# ardOnTimer.net
KiCad netlist of a schematic drawn in EAGLE
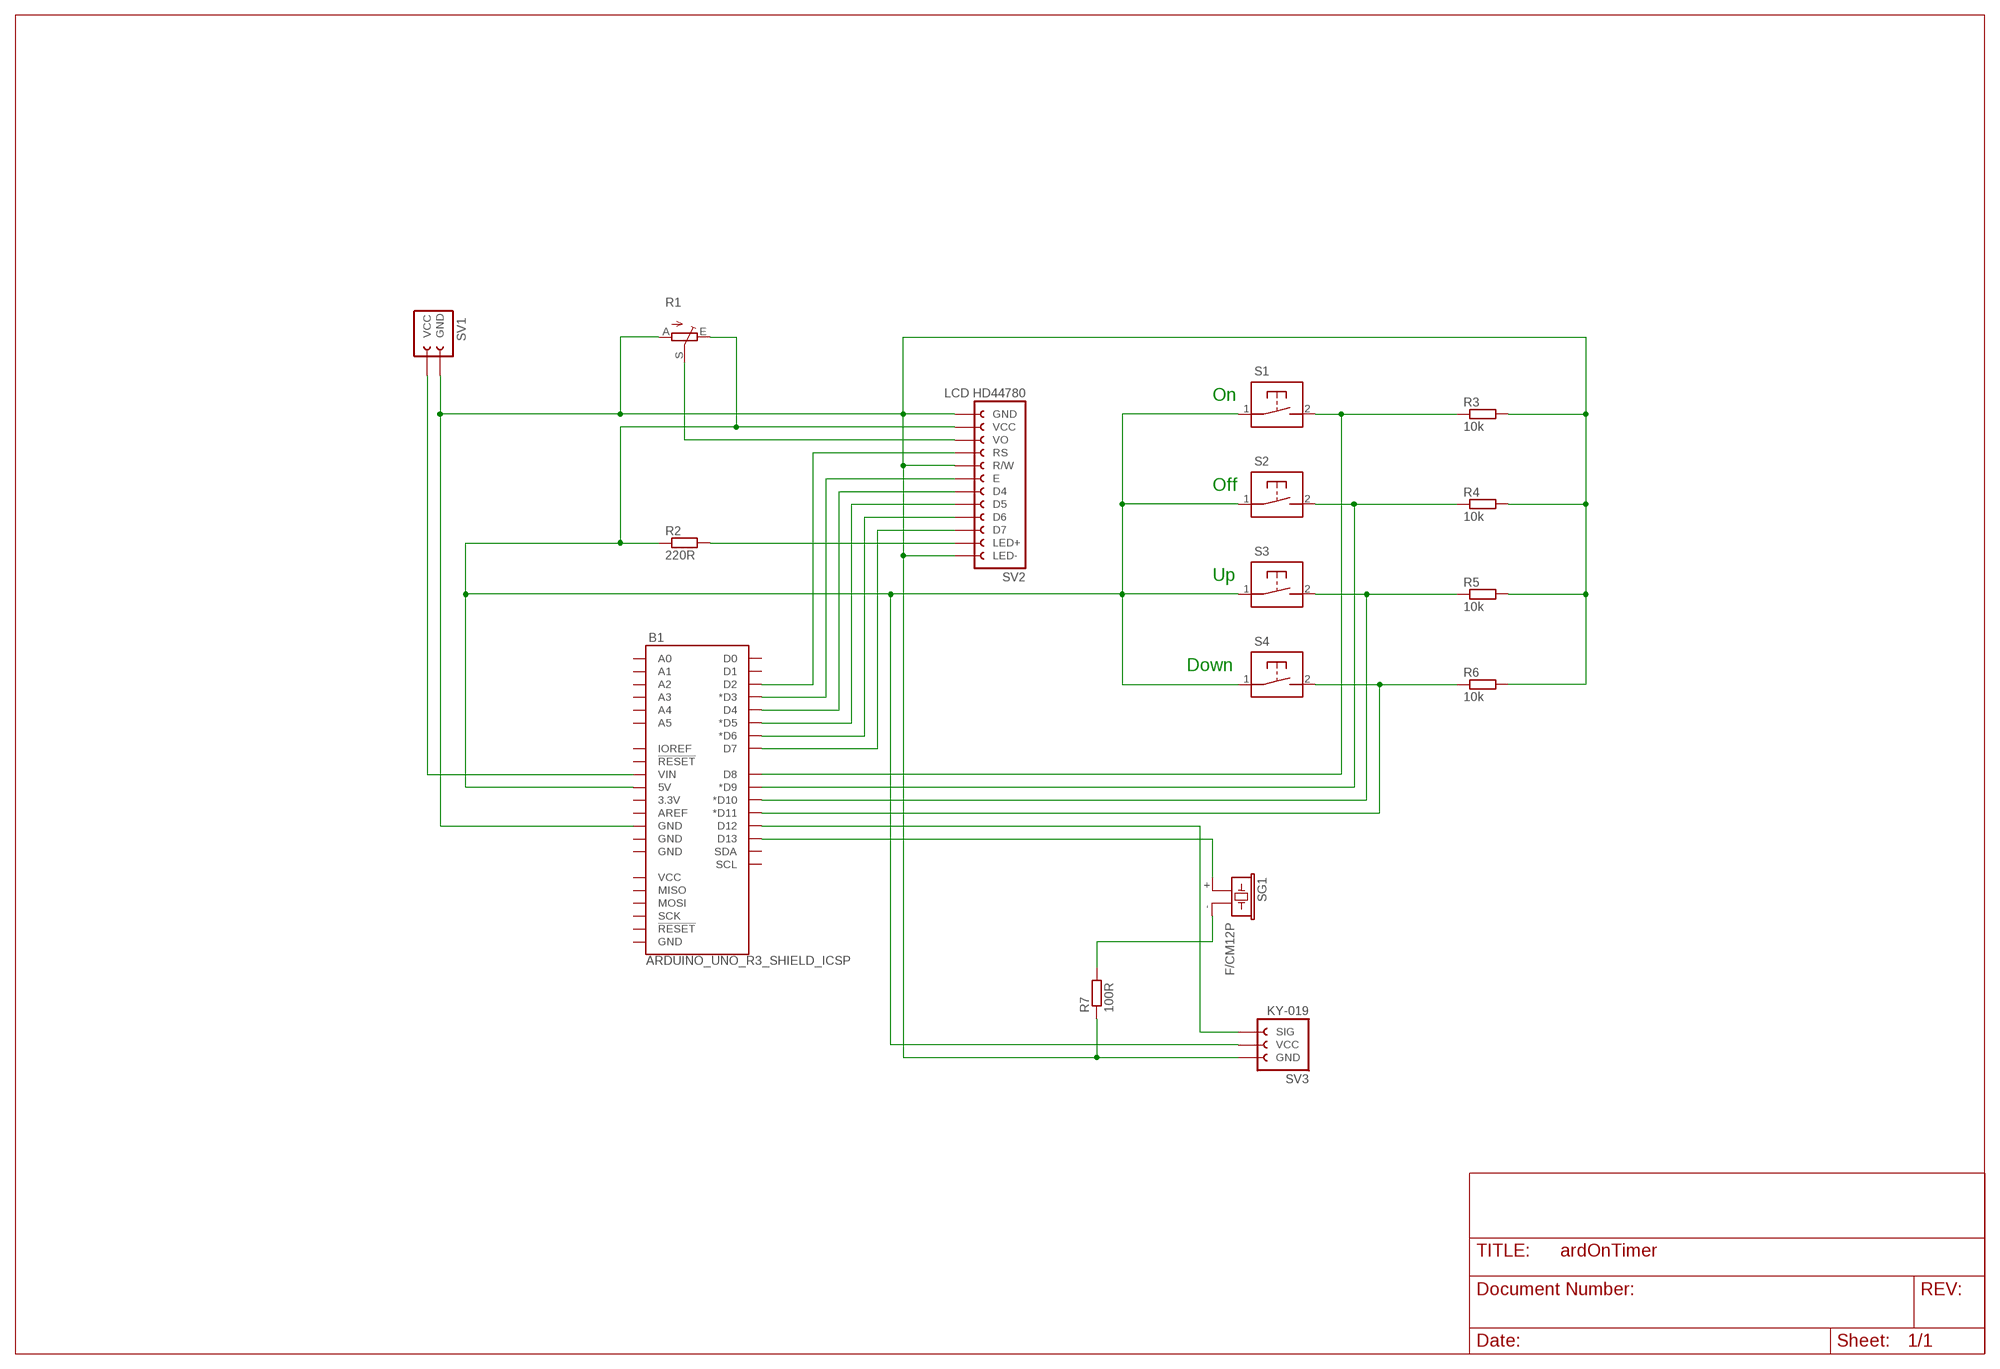
[diagram p0: schematic, sheet 1]

(export (version "E")
  (design (tool "Eeschema 10.0.6"))
  (components
    (comp (ref "B1")
      (value "ARDUINO_UNO_R3_SHIELD_ICSP")
      (footprint "eagle-import:UNO_R3_SHIELD_ICSP")
      (libsource (lib "eagle-import") (part "ARDUINO_UNO_R3_SHIELD_ICSP"))
    )
    (comp (ref "R1")
      (value "POTENTIOMETER_CA6VCA6V")
      (footprint "eagle-import:CA6V")
      (libsource (lib "eagle-import") (part "POTENTIOMETER_CA6VCA6V"))
    )
    (comp (ref "R2")
      (value "220R")
      (footprint "eagle-import:0204_7")
      (libsource (lib "eagle-import") (part "R-EU_0204/7"))
    )
    (comp (ref "R3")
      (value "10k")
      (footprint "eagle-import:0204_7")
      (libsource (lib "eagle-import") (part "R-EU_0204/7"))
    )
    (comp (ref "R4")
      (value "10k")
      (footprint "eagle-import:0204_7")
      (libsource (lib "eagle-import") (part "R-EU_0204/7"))
    )
    (comp (ref "R5")
      (value "10k")
      (footprint "eagle-import:0204_7")
      (libsource (lib "eagle-import") (part "R-EU_0204/7"))
    )
    (comp (ref "R6")
      (value "10k")
      (footprint "eagle-import:0204_7")
      (libsource (lib "eagle-import") (part "R-EU_0204/7"))
    )
    (comp (ref "R7")
      (value "100R")
      (footprint "eagle-import:0204_7")
      (libsource (lib "eagle-import") (part "R-EU_0204/7"))
    )
    (comp (ref "S1")
      (value "NO_SWITCH_2-PIN-FEMALE_HEADER")
      (footprint "eagle-import:NO_SWITCH_2-PIN-FEMALE_HEADER")
      (fields (field (name "MPN") "B3F-3100"))
      (libsource (lib "eagle-import") (part "NO_SWITCH_2-PIN-FEMALE_HEADER"))
    )
    (comp (ref "S2")
      (value "NO_SWITCH_2-PIN-FEMALE_HEADER")
      (footprint "eagle-import:NO_SWITCH_2-PIN-FEMALE_HEADER")
      (fields (field (name "MPN") "B3F-3100"))
      (libsource (lib "eagle-import") (part "NO_SWITCH_2-PIN-FEMALE_HEADER"))
    )
    (comp (ref "S3")
      (value "NO_SWITCH_2-PIN-FEMALE_HEADER")
      (footprint "eagle-import:NO_SWITCH_2-PIN-FEMALE_HEADER")
      (fields (field (name "MPN") "B3F-3100"))
      (libsource (lib "eagle-import") (part "NO_SWITCH_2-PIN-FEMALE_HEADER"))
    )
    (comp (ref "S4")
      (value "NO_SWITCH_2-PIN-FEMALE_HEADER")
      (footprint "eagle-import:NO_SWITCH_2-PIN-FEMALE_HEADER")
      (fields (field (name "MPN") "B3F-3100"))
      (libsource (lib "eagle-import") (part "NO_SWITCH_2-PIN-FEMALE_HEADER"))
    )
    (comp (ref "SG1")
      (value "F/CM12P")
      (footprint "eagle-import:F_CM12P")
      (libsource (lib "eagle-import") (part "F/CM12P"))
    )
    (comp (ref "SV1")
      (value "POWER_IN-2-PIN_FEMALE_HEADER")
      (footprint "eagle-import:POWER_IN-2-PIN_FEMALE_HEADER")
      (libsource (lib "eagle-import") (part "POWER_IN-2-PIN_FEMALE_HEADER"))
    )
    (comp (ref "SV2")
      (value "LCD-HD44780-12-PIN_FEMALE_HEADER")
      (footprint "eagle-import:LCD-HD44780-12-PIN_FEMALE_HEADER")
      (libsource (lib "eagle-import") (part "LCD-HD44780-12-PIN_FEMALE_HEADER"))
    )
    (comp (ref "SV3")
      (value "KY-019_3-PIN_FEMALE_HEADERANGLED_W_MOUNT_HOLES")
      (footprint "eagle-import:KY-019_3-PIN_FEMALE_HEADER_ANGLED_W_MOUNT_HOLES")
      (libsource (lib "eagle-import") (part "KY-019_3-PIN_FEMALE_HEADERANGLED_W_MOUNT_HOLES"))
    )
  )
  (nets
    (net (code "1") (name "Net-(B1-*D3)") (class "Default")
      (node (ref "B1") (pin "D3") (pinfunction "*D3_D3") (pintype "bidirectional"))
      (node (ref "SV2") (pin "E") (pinfunction "E_E") (pintype "passive"))
    )
    (net (code "2") (name "Net-(B1-*D5)") (class "Default")
      (node (ref "B1") (pin "D5") (pinfunction "*D5_D5") (pintype "bidirectional"))
      (node (ref "SV2") (pin "D5") (pinfunction "D5_D5") (pintype "passive"))
    )
    (net (code "3") (name "Net-(B1-*D6)") (class "Default")
      (node (ref "B1") (pin "D6") (pinfunction "*D6_D6") (pintype "bidirectional"))
      (node (ref "SV2") (pin "D6") (pinfunction "D6_D6") (pintype "passive"))
    )
    (net (code "4") (name "Net-(B1-*D9)") (class "Default")
      (node (ref "B1") (pin "D9") (pinfunction "*D9_D9") (pintype "bidirectional"))
      (node (ref "R4") (pin "1") (pinfunction "1_1") (pintype "passive"))
      (node (ref "S2") (pin "2") (pinfunction "S_2") (pintype "passive"))
    )
    (net (code "5") (name "Net-(B1-*D10)") (class "Default")
      (node (ref "B1") (pin "D10") (pinfunction "*D10_D10") (pintype "bidirectional"))
      (node (ref "R5") (pin "1") (pinfunction "1_1") (pintype "passive"))
      (node (ref "S3") (pin "2") (pinfunction "S_2") (pintype "passive"))
    )
    (net (code "6") (name "Net-(B1-*D11)") (class "Default")
      (node (ref "B1") (pin "D11") (pinfunction "*D11_D11") (pintype "bidirectional"))
      (node (ref "R6") (pin "1") (pinfunction "1_1") (pintype "passive"))
      (node (ref "S4") (pin "2") (pinfunction "S_2") (pintype "passive"))
    )
    (net (code "7") (name "Net-(B1-GND-PadGND@2)") (class "Default")
      (node (ref "B1") (pin "GND@2") (pinfunction "GND_GND@2") (pintype "bidirectional"))
      (node (ref "R1") (pin "A") (pinfunction "A_A") (pintype "passive"))
      (node (ref "R3") (pin "2") (pinfunction "2_2") (pintype "passive"))
      (node (ref "R4") (pin "2") (pinfunction "2_2") (pintype "passive"))
      (node (ref "R5") (pin "2") (pinfunction "2_2") (pintype "passive"))
      (node (ref "R6") (pin "2") (pinfunction "2_2") (pintype "passive"))
      (node (ref "R7") (pin "1") (pinfunction "1_1") (pintype "passive"))
      (node (ref "SV1") (pin "GND") (pinfunction "GND_GND") (pintype "passive"))
      (node (ref "SV2") (pin "GND") (pinfunction "GND_GND") (pintype "passive"))
      (node (ref "SV2") (pin "LED-") (pinfunction "LED-_LED-") (pintype "passive"))
      (node (ref "SV2") (pin "R/W") (pinfunction "R/W_R/W") (pintype "passive"))
      (node (ref "SV3") (pin "GND") (pinfunction "GND_GND") (pintype "passive"))
    )
    (net (code "8") (name "Net-(B1-PadD2)") (class "Default")
      (node (ref "B1") (pin "D2") (pinfunction "D2_D2") (pintype "bidirectional"))
      (node (ref "SV2") (pin "RS") (pinfunction "RS_RS") (pintype "passive"))
    )
    (net (code "9") (name "Net-(B1-PadD4)") (class "Default")
      (node (ref "B1") (pin "D4") (pinfunction "D4_D4") (pintype "bidirectional"))
      (node (ref "SV2") (pin "D4") (pinfunction "D4_D4") (pintype "passive"))
    )
    (net (code "10") (name "Net-(B1-PadD7)") (class "Default")
      (node (ref "B1") (pin "D7") (pinfunction "D7_D7") (pintype "bidirectional"))
      (node (ref "SV2") (pin "D7") (pinfunction "D7_D7") (pintype "passive"))
    )
    (net (code "11") (name "Net-(B1-PadD12)") (class "Default")
      (node (ref "B1") (pin "D12") (pinfunction "D12_D12") (pintype "bidirectional"))
      (node (ref "SV3") (pin "SIG") (pinfunction "SIG_SIG") (pintype "passive"))
    )
    (net (code "12") (name "Net-(B1-PadVIN)") (class "Default")
      (node (ref "B1") (pin "VIN") (pinfunction "VIN_VIN") (pintype "bidirectional"))
      (node (ref "SV1") (pin "VCC") (pinfunction "VCC_VCC") (pintype "passive"))
    )
    (net (code "13") (name "Net-(R1-PadS)") (class "Default")
      (node (ref "R1") (pin "S") (pinfunction "S_S") (pintype "passive"))
      (node (ref "SV2") (pin "VO") (pinfunction "VO_VO") (pintype "passive"))
    )
    (net (code "14") (name "Net-(R2-Pad2)") (class "Default")
      (node (ref "R2") (pin "2") (pinfunction "2_2") (pintype "passive"))
      (node (ref "SV2") (pin "LED+") (pinfunction "LED+_LED+") (pintype "passive"))
    )
    (net (code "15") (name "Net-(S1-P)") (class "Default")
      (node (ref "B1") (pin "5V") (pinfunction "5V_5V") (pintype "bidirectional"))
      (node (ref "R1") (pin "E") (pinfunction "E_E") (pintype "passive"))
      (node (ref "R2") (pin "1") (pinfunction "1_1") (pintype "passive"))
      (node (ref "S1") (pin "1") (pinfunction "P_1") (pintype "passive"))
      (node (ref "S2") (pin "1") (pinfunction "P_1") (pintype "passive"))
      (node (ref "S3") (pin "1") (pinfunction "P_1") (pintype "passive"))
      (node (ref "S4") (pin "1") (pinfunction "P_1") (pintype "passive"))
      (node (ref "SV2") (pin "VCC") (pinfunction "VCC_VCC") (pintype "passive"))
      (node (ref "SV3") (pin "VCC") (pinfunction "VCC_VCC") (pintype "passive"))
    )
    (net (code "16") (name "Net-(S1-S)") (class "Default")
      (node (ref "B1") (pin "D8") (pinfunction "D8_D8") (pintype "bidirectional"))
      (node (ref "R3") (pin "1") (pinfunction "1_1") (pintype "passive"))
      (node (ref "S1") (pin "2") (pinfunction "S_2") (pintype "passive"))
    )
    (net (code "17") (name "Net-(SG1-1)") (class "Default")
      (node (ref "B1") (pin "D13") (pinfunction "D13_D13") (pintype "bidirectional"))
      (node (ref "SG1") (pin "+") (pinfunction "1_+") (pintype "passive"))
    )
    (net (code "18") (name "Net-(SG1-2)") (class "Default")
      (node (ref "R7") (pin "2") (pinfunction "2_2") (pintype "passive"))
      (node (ref "SG1") (pin "-") (pinfunction "2_-") (pintype "passive"))
    )
    (net (code "19") (name "unconnected-(B1-D0-PadRX)") (class "Default")
      (node (ref "B1") (pin "RX") (pinfunction "D0_RX") (pintype "bidirectional"))
    )
    (net (code "20") (name "unconnected-(B1-D1-PadTX)") (class "Default")
      (node (ref "B1") (pin "TX") (pinfunction "D1_TX") (pintype "bidirectional"))
    )
    (net (code "21") (name "unconnected-(B1-GND-PadGND@0)") (class "Default")
      (node (ref "B1") (pin "GND@0") (pinfunction "GND_GND@0") (pintype "bidirectional"))
    )
    (net (code "22") (name "unconnected-(B1-GND-PadGND@1)") (class "Default")
      (node (ref "B1") (pin "GND@1") (pinfunction "GND_GND@1") (pintype "bidirectional"))
    )
    (net (code "23") (name "unconnected-(B1-GND-PadGND_ICSP)") (class "Default")
      (node (ref "B1") (pin "GND_ICSP") (pinfunction "GND_GND_ICSP") (pintype "bidirectional"))
    )
    (net (code "24") (name "unconnected-(B1-Pad3.3V)") (class "Default")
      (node (ref "B1") (pin "3.3V") (pinfunction "3.3V_3.3V") (pintype "bidirectional"))
    )
    (net (code "25") (name "unconnected-(B1-PadA0)") (class "Default")
      (node (ref "B1") (pin "A0") (pinfunction "A0_A0") (pintype "bidirectional"))
    )
    (net (code "26") (name "unconnected-(B1-PadA1)") (class "Default")
      (node (ref "B1") (pin "A1") (pinfunction "A1_A1") (pintype "bidirectional"))
    )
    (net (code "27") (name "unconnected-(B1-PadA2)") (class "Default")
      (node (ref "B1") (pin "A2") (pinfunction "A2_A2") (pintype "bidirectional"))
    )
    (net (code "28") (name "unconnected-(B1-PadA3)") (class "Default")
      (node (ref "B1") (pin "A3") (pinfunction "A3_A3") (pintype "bidirectional"))
    )
    (net (code "29") (name "unconnected-(B1-PadA4)") (class "Default")
      (node (ref "B1") (pin "A4") (pinfunction "A4_A4") (pintype "bidirectional"))
    )
    (net (code "30") (name "unconnected-(B1-PadA5)") (class "Default")
      (node (ref "B1") (pin "A5") (pinfunction "A5_A5") (pintype "bidirectional"))
    )
    (net (code "31") (name "unconnected-(B1-PadAREF)") (class "Default")
      (node (ref "B1") (pin "AREF") (pinfunction "AREF_AREF") (pintype "bidirectional"))
    )
    (net (code "32") (name "unconnected-(B1-PadIOREF)") (class "Default")
      (node (ref "B1") (pin "IOREF") (pinfunction "IOREF_IOREF") (pintype "bidirectional"))
    )
    (net (code "33") (name "unconnected-(B1-PadMISO)") (class "Default")
      (node (ref "B1") (pin "MISO") (pinfunction "MISO_MISO") (pintype "bidirectional"))
    )
    (net (code "34") (name "unconnected-(B1-PadMOSI)") (class "Default")
      (node (ref "B1") (pin "MOSI") (pinfunction "MOSI_MOSI") (pintype "bidirectional"))
    )
    (net (code "35") (name "unconnected-(B1-PadSCK)") (class "Default")
      (node (ref "B1") (pin "SCK") (pinfunction "SCK_SCK") (pintype "bidirectional"))
    )
    (net (code "36") (name "unconnected-(B1-PadSCL)") (class "Default")
      (node (ref "B1") (pin "SCL") (pinfunction "SCL_SCL") (pintype "bidirectional"))
    )
    (net (code "37") (name "unconnected-(B1-PadSDA)") (class "Default")
      (node (ref "B1") (pin "SDA") (pinfunction "SDA_SDA") (pintype "bidirectional"))
    )
    (net (code "38") (name "unconnected-(B1-VCC-Pad5V_ICSP)") (class "Default")
      (node (ref "B1") (pin "5V_ICSP") (pinfunction "VCC_5V_ICSP") (pintype "bidirectional"))
    )
    (net (code "39") (name "unconnected-(B1-~{RESET}-PadRES)") (class "Default")
      (node (ref "B1") (pin "RES") (pinfunction "~{RESET}_RES") (pintype "bidirectional"))
    )
    (net (code "40") (name "unconnected-(B1-~{RESET}-PadRST_ICSP)") (class "Default")
      (node (ref "B1") (pin "RST_ICSP") (pinfunction "~{RESET}_RST_ICSP") (pintype "bidirectional"))
    )
  )
)
